# FC_V3_0_SCH_2021-06-05_17-42-28.net
KiCad netlist of a schematic drawn in Altium Designer
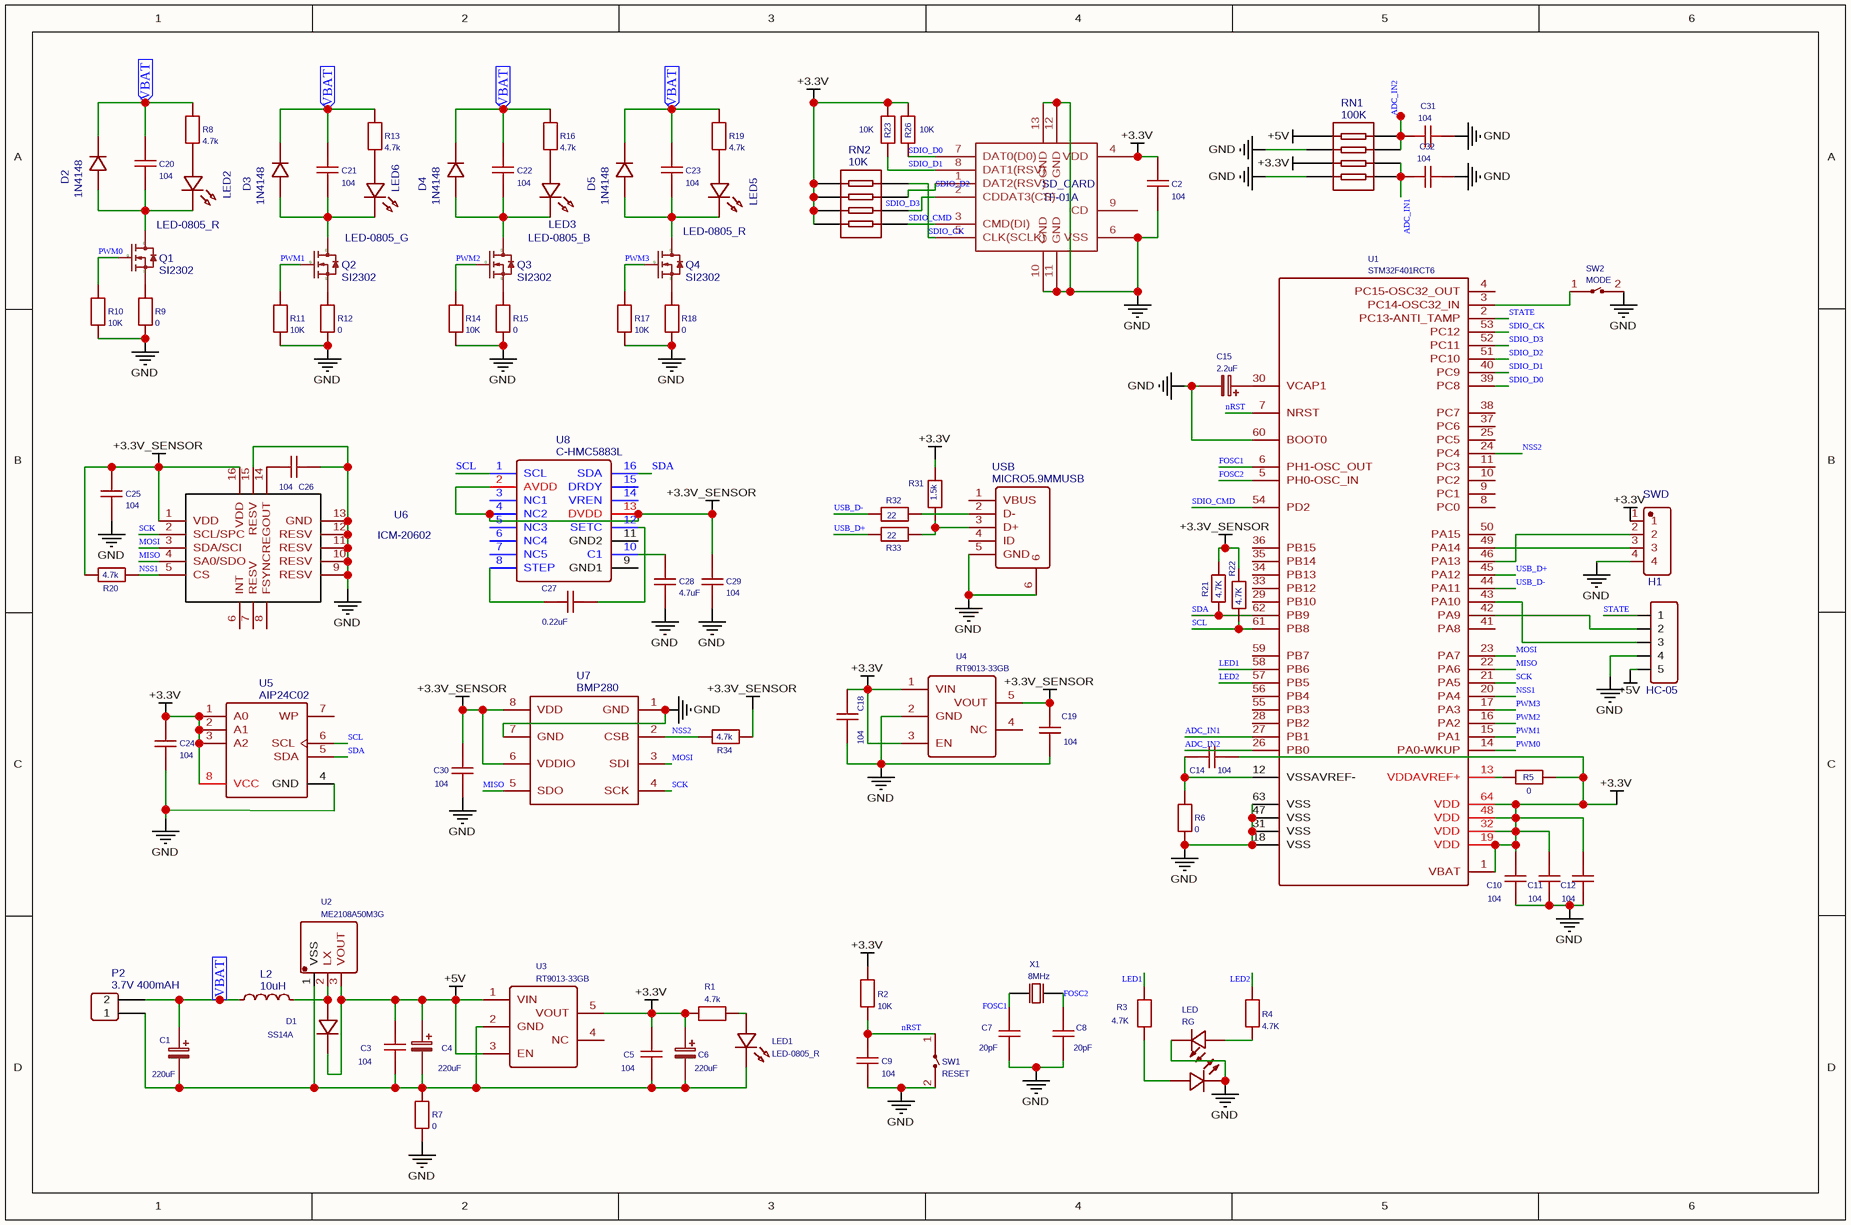
[diagram p0: FC_V3_0_SCH_2021-06-05_17-42-28.schdoc]

(export (version "E")
  (design (tool "Eeschema 10.0.6"))
  (components
    (comp (ref "C1")
      (value "220uF")
      (fields (field (name "CONTRIBUTOR") "LCEDA_Lib"))
      (libsource (lib "altium-import") (part "root_3_220uF_"))
    )
    (comp (ref "C2")
      (value "104")
      (fields (field (name "CONTRIBUTOR") "LCEDA_Lib"))
      (libsource (lib "altium-import") (part "root_1_104_"))
    )
    (comp (ref "C3")
      (value "104")
      (fields (field (name "CONTRIBUTOR") "LCEDA_Lib"))
      (libsource (lib "altium-import") (part "root_1_104_"))
    )
    (comp (ref "C4")
      (value "220uF")
      (fields (field (name "CONTRIBUTOR") "LCEDA_Lib"))
      (libsource (lib "altium-import") (part "root_3_220uF_"))
    )
    (comp (ref "C5")
      (value "104")
      (fields (field (name "CONTRIBUTOR") "LCEDA_Lib"))
      (libsource (lib "altium-import") (part "root_1_104_"))
    )
    (comp (ref "C6")
      (value "220uF")
      (fields (field (name "CONTRIBUTOR") "LCEDA_Lib"))
      (libsource (lib "altium-import") (part "root_3_220uF_"))
    )
    (comp (ref "C7")
      (value "20pF")
      (fields (field (name "CONTRIBUTOR") "LCEDA_Lib"))
      (libsource (lib "altium-import") (part "root_1_20pF_"))
    )
    (comp (ref "C8")
      (value "20pF")
      (fields (field (name "CONTRIBUTOR") "LCEDA_Lib"))
      (libsource (lib "altium-import") (part "root_1_20pF_"))
    )
    (comp (ref "C9")
      (value "104")
      (fields (field (name "CONTRIBUTOR") "LCEDA_Lib"))
      (libsource (lib "altium-import") (part "root_1_104_"))
    )
    (comp (ref "C10")
      (value "104")
      (fields (field (name "CONTRIBUTOR") "LCEDA_Lib"))
      (libsource (lib "altium-import") (part "root_1_104_"))
    )
    (comp (ref "C11")
      (value "104")
      (fields (field (name "CONTRIBUTOR") "LCEDA_Lib"))
      (libsource (lib "altium-import") (part "root_1_104_"))
    )
    (comp (ref "C12")
      (value "104")
      (fields (field (name "CONTRIBUTOR") "LCEDA_Lib"))
      (libsource (lib "altium-import") (part "root_1_104_"))
    )
    (comp (ref "C14")
      (value "104")
      (fields (field (name "CONTRIBUTOR") "LCEDA_Lib"))
      (libsource (lib "altium-import") (part "root_0_104_"))
    )
    (comp (ref "C15")
      (value "2.2uF")
      (fields (field (name "CONTRIBUTOR") "LCEDA_Lib"))
      (libsource (lib "altium-import") (part "root_2_2.2uF_"))
    )
    (comp (ref "C18")
      (value "104")
      (fields (field (name "CONTRIBUTOR") "LCEDA_Lib"))
      (libsource (lib "altium-import") (part "root_1_104_"))
    )
    (comp (ref "C19")
      (value "104")
      (fields (field (name "CONTRIBUTOR") "LCEDA_Lib"))
      (libsource (lib "altium-import") (part "root_1_104_"))
    )
    (comp (ref "C20")
      (value "104")
      (fields (field (name "CONTRIBUTOR") "LCEDA_Lib"))
      (libsource (lib "altium-import") (part "root_1_104_"))
    )
    (comp (ref "C21")
      (value "104")
      (fields (field (name "CONTRIBUTOR") "LCEDA_Lib"))
      (libsource (lib "altium-import") (part "root_1_104_"))
    )
    (comp (ref "C22")
      (value "104")
      (fields (field (name "CONTRIBUTOR") "LCEDA_Lib"))
      (libsource (lib "altium-import") (part "root_1_104_"))
    )
    (comp (ref "C23")
      (value "104")
      (fields (field (name "CONTRIBUTOR") "LCEDA_Lib"))
      (libsource (lib "altium-import") (part "root_1_104_"))
    )
    (comp (ref "C24")
      (value "104")
      (fields (field (name "CONTRIBUTOR") "LCEDA_Lib"))
      (libsource (lib "altium-import") (part "root_1_104_"))
    )
    (comp (ref "C25")
      (value "104")
      (fields (field (name "CONTRIBUTOR") "LCEDA_Lib"))
      (libsource (lib "altium-import") (part "root_3_104_"))
    )
    (comp (ref "C26")
      (value "104")
      (fields (field (name "CONTRIBUTOR") "LCEDA_Lib"))
      (libsource (lib "altium-import") (part "root_0_104_"))
    )
    (comp (ref "C27")
      (value "0.22uF")
      (fields (field (name "CONTRIBUTOR") "LCEDA_Lib"))
      (libsource (lib "altium-import") (part "root_0_0.22uF_"))
    )
    (comp (ref "C28")
      (value "4.7uF")
      (fields (field (name "CONTRIBUTOR") "LCEDA_Lib"))
      (libsource (lib "altium-import") (part "root_1_4.7uF_"))
    )
    (comp (ref "C29")
      (value "104")
      (fields (field (name "CONTRIBUTOR") "LCEDA_Lib"))
      (libsource (lib "altium-import") (part "root_1_104_"))
    )
    (comp (ref "C30")
      (value "104")
      (fields (field (name "CONTRIBUTOR") "LCEDA_Lib"))
      (libsource (lib "altium-import") (part "root_1_104_"))
    )
    (comp (ref "C31")
      (value "104")
      (fields (field (name "CONTRIBUTOR") "LCEDA_Lib"))
      (libsource (lib "altium-import") (part "root_2_104_"))
    )
    (comp (ref "C32")
      (value "104")
      (fields (field (name "CONTRIBUTOR") "LCEDA_Lib"))
      (libsource (lib "altium-import") (part "root_2_104_"))
    )
    (comp (ref "D1")
      (value "SS14A")
      (fields (field (name "BOM_SUPPLIER PART") "C211770") (field (name "CONTRIBUTOR") "LCSC"))
      (libsource (lib "altium-import") (part "root_1_SS14A_"))
    )
    (comp (ref "D2")
      (value "1N4148")
      (fields (field (name "BOM_SUPPLIER PART") "C14516") (field (name "CONTRIBUTOR") "LCEDA_Lib"))
      (libsource (lib "altium-import") (part "root_1_1N4148_"))
    )
    (comp (ref "D3")
      (value "1N4148")
      (fields (field (name "BOM_SUPPLIER PART") "C14516") (field (name "CONTRIBUTOR") "LCEDA_Lib"))
      (libsource (lib "altium-import") (part "root_1_1N4148_"))
    )
    (comp (ref "D4")
      (value "1N4148")
      (fields (field (name "BOM_SUPPLIER PART") "C14516") (field (name "CONTRIBUTOR") "LCEDA_Lib"))
      (libsource (lib "altium-import") (part "root_1_1N4148_"))
    )
    (comp (ref "D5")
      (value "1N4148")
      (fields (field (name "BOM_SUPPLIER PART") "C14516") (field (name "CONTRIBUTOR") "LCEDA_Lib"))
      (libsource (lib "altium-import") (part "root_1_1N4148_"))
    )
    (comp (ref "H1")
      (value "HC-05")
      (fields (field (name "BOM_SUPPLIER PART") "C50950") (field (name "CONTRIBUTOR") "LCEDA_Lib"))
      (libsource (lib "altium-import") (part "root_0_HC-05_"))
    )
    (comp (ref "L2")
      (value "10uH")
      (fields
        (field (name "BOM_SUPPLIER PART") "C207827")
        (field (name "BOM_MANUFACTURER PART") "SLO0420H1R5MTT")
        (field (name "CONTRIBUTOR") "LCSC")
      )
      (libsource (lib "altium-import") (part "root_0_10uH_"))
    )
    (comp (ref "LED")
      (value "RG")
      (fields
        (field (name "BOM_SUPPLIER PART") "C409778")
        (field (name "BOM_MANUFACTURER PART") "MHP3528URUGCT")
        (field (name "CONTRIBUTOR") "LCSC")
      )
      (libsource (lib "altium-import") (part "root_0_RG_"))
    )
    (comp (ref "LED1")
      (value "LED-0805_R")
      (fields
        (field (name "BOM_MANUFACTURER PART") "17-21SURC/S530-A3/TR8")
        (field (name "BOM_SUPPLIER PART") "C72037")
        (field (name "CONTRIBUTOR") "LCEDA_Lib")
      )
      (libsource (lib "altium-import") (part "root_3_LED-0805_R_"))
    )
    (comp (ref "LED2")
      (value "LED-0805_R")
      (fields
        (field (name "BOM_MANUFACTURER PART") "17-21SURC/S530-A3/TR8")
        (field (name "BOM_SUPPLIER PART") "C72037")
        (field (name "CONTRIBUTOR") "LCEDA_Lib")
      )
      (libsource (lib "altium-import") (part "root_3_LED-0805_R_"))
    )
    (comp (ref "LED3")
      (value "LED-0805_B")
      (fields
        (field (name "BOM_MANUFACTURER PART") "D-B080508B1-KS2")
        (field (name "BOM_SUPPLIER PART") "C108412")
        (field (name "CONTRIBUTOR") "LCEDA_Lib")
      )
      (libsource (lib "altium-import") (part "root_3_LED-0805_B_"))
    )
    (comp (ref "LED5")
      (value "LED-0805_R")
      (fields
        (field (name "BOM_MANUFACTURER PART") "17-21SURC/S530-A3/TR8")
        (field (name "BOM_SUPPLIER PART") "C72037")
        (field (name "CONTRIBUTOR") "LCEDA_Lib")
      )
      (libsource (lib "altium-import") (part "root_3_LED-0805_R_"))
    )
    (comp (ref "LED6")
      (value "LED-0805_G")
      (fields
        (field (name "BOM_MANUFACTURER PART") "NCD0805G1")
        (field (name "BOM_SUPPLIER PART") "C84260")
        (field (name "CONTRIBUTOR") "LCEDA_Lib")
      )
      (libsource (lib "altium-import") (part "root_3_LED-0805_G_"))
    )
    (comp (ref "P2")
      (value "3.7V 400mAH")
      (fields
        (field (name "BOM_MANUFACTURER PART") "2.54mm 1*2P")
        (field (name "BOM_SUPPLIER PART") "C36717")
      )
      (libsource (lib "altium-import") (part "root_2_3.7V 400mAH_"))
    )
    (comp (ref "Q1")
      (value "SI2302")
      (fields (field (name "BOM_SUPPLIER PART") "C181087") (field (name "CONTRIBUTOR") "LCSC"))
      (libsource (lib "altium-import") (part "root_0_SI2302_"))
    )
    (comp (ref "Q2")
      (value "SI2302")
      (fields (field (name "BOM_SUPPLIER PART") "C181087") (field (name "CONTRIBUTOR") "LCSC"))
      (libsource (lib "altium-import") (part "root_0_SI2302_"))
    )
    (comp (ref "Q3")
      (value "SI2302")
      (fields (field (name "BOM_SUPPLIER PART") "C181087") (field (name "CONTRIBUTOR") "LCSC"))
      (libsource (lib "altium-import") (part "root_0_SI2302_"))
    )
    (comp (ref "Q4")
      (value "SI2302")
      (fields (field (name "BOM_SUPPLIER PART") "C181087") (field (name "CONTRIBUTOR") "LCSC"))
      (libsource (lib "altium-import") (part "root_0_SI2302_"))
    )
    (comp (ref "R1")
      (value "4.7k")
      (fields (field (name "CONTRIBUTOR") "LCEDA_Lib"))
      (libsource (lib "altium-import") (part "root_0_4.7k_"))
    )
    (comp (ref "R2")
      (value "10K")
      (fields (field (name "CONTRIBUTOR") "LCEDA_Lib"))
      (libsource (lib "altium-import") (part "root_1_10K_"))
    )
    (comp (ref "R3")
      (value "4.7K")
      (fields (field (name "CONTRIBUTOR") "LCEDA_Lib"))
      (libsource (lib "altium-import") (part "root_1_4.7K_"))
    )
    (comp (ref "R4")
      (value "4.7K")
      (fields (field (name "CONTRIBUTOR") "LCEDA_Lib"))
      (libsource (lib "altium-import") (part "root_1_4.7K_"))
    )
    (comp (ref "R5")
      (value "0")
      (fields (field (name "CONTRIBUTOR") "LCEDA_Lib"))
      (libsource (lib "altium-import") (part "root_0_0_"))
    )
    (comp (ref "R6")
      (value "0")
      (fields (field (name "CONTRIBUTOR") "LCEDA_Lib"))
      (libsource (lib "altium-import") (part "root_3_0_"))
    )
    (comp (ref "R7")
      (value "0")
      (fields (field (name "CONTRIBUTOR") "LCEDA_Lib"))
      (libsource (lib "altium-import") (part "root_3_0_"))
    )
    (comp (ref "R8")
      (value "4.7k")
      (fields (field (name "CONTRIBUTOR") "LCEDA_Lib"))
      (libsource (lib "altium-import") (part "root_1_4.7k_"))
    )
    (comp (ref "R9")
      (value "0")
      (fields (field (name "CONTRIBUTOR") "LCEDA_Lib"))
      (libsource (lib "altium-import") (part "root_3_0_"))
    )
    (comp (ref "R10")
      (value "10K")
      (fields (field (name "CONTRIBUTOR") "LCEDA_Lib"))
      (libsource (lib "altium-import") (part "root_1_10K_"))
    )
    (comp (ref "R11")
      (value "10K")
      (fields (field (name "CONTRIBUTOR") "LCEDA_Lib"))
      (libsource (lib "altium-import") (part "root_1_10K_"))
    )
    (comp (ref "R12")
      (value "0")
      (fields (field (name "CONTRIBUTOR") "LCEDA_Lib"))
      (libsource (lib "altium-import") (part "root_3_0_"))
    )
    (comp (ref "R13")
      (value "4.7k")
      (fields (field (name "CONTRIBUTOR") "LCEDA_Lib"))
      (libsource (lib "altium-import") (part "root_1_4.7k_"))
    )
    (comp (ref "R14")
      (value "10K")
      (fields (field (name "CONTRIBUTOR") "LCEDA_Lib"))
      (libsource (lib "altium-import") (part "root_1_10K_"))
    )
    (comp (ref "R15")
      (value "0")
      (fields (field (name "CONTRIBUTOR") "LCEDA_Lib"))
      (libsource (lib "altium-import") (part "root_3_0_"))
    )
    (comp (ref "R16")
      (value "4.7k")
      (fields (field (name "CONTRIBUTOR") "LCEDA_Lib"))
      (libsource (lib "altium-import") (part "root_1_4.7k_"))
    )
    (comp (ref "R17")
      (value "10K")
      (fields (field (name "CONTRIBUTOR") "LCEDA_Lib"))
      (libsource (lib "altium-import") (part "root_1_10K_"))
    )
    (comp (ref "R18")
      (value "0")
      (fields (field (name "CONTRIBUTOR") "LCEDA_Lib"))
      (libsource (lib "altium-import") (part "root_3_0_"))
    )
    (comp (ref "R19")
      (value "4.7k")
      (fields (field (name "CONTRIBUTOR") "LCEDA_Lib"))
      (libsource (lib "altium-import") (part "root_1_4.7k_"))
    )
    (comp (ref "R20")
      (value "4.7k")
      (fields (field (name "CONTRIBUTOR") "LCEDA_Lib"))
      (libsource (lib "altium-import") (part "root_2_4.7k_"))
    )
    (comp (ref "R21")
      (value "4.7K")
      (fields (field (name "CONTRIBUTOR") "LCEDA_Lib"))
      (libsource (lib "altium-import") (part "root_3_4.7K_"))
    )
    (comp (ref "R22")
      (value "4.7K")
      (fields (field (name "CONTRIBUTOR") "LCEDA_Lib"))
      (libsource (lib "altium-import") (part "root_3_4.7K_"))
    )
    (comp (ref "R23")
      (value "10K")
      (fields (field (name "CONTRIBUTOR") "LCEDA_Lib"))
      (libsource (lib "altium-import") (part "root_3_10K_"))
    )
    (comp (ref "R26")
      (value "10K")
      (fields (field (name "CONTRIBUTOR") "LCEDA_Lib"))
      (libsource (lib "altium-import") (part "root_3_10K_"))
    )
    (comp (ref "R31")
      (value "1.5k")
      (fields (field (name "CONTRIBUTOR") "LCEDA_Lib"))
      (libsource (lib "altium-import") (part "root_1_1.5k_"))
    )
    (comp (ref "R32")
      (value "22")
      (fields (field (name "CONTRIBUTOR") "LCEDA_Lib"))
      (libsource (lib "altium-import") (part "root_2_22_"))
    )
    (comp (ref "R33")
      (value "22")
      (fields (field (name "CONTRIBUTOR") "LCEDA_Lib"))
      (libsource (lib "altium-import") (part "root_2_22_"))
    )
    (comp (ref "R34")
      (value "4.7k")
      (fields (field (name "CONTRIBUTOR") "LCEDA_Lib"))
      (libsource (lib "altium-import") (part "root_2_4.7k_"))
    )
    (comp (ref "RN1")
      (value "100K")
      (fields
        (field (name "BOM_MANUFACTURER PART") "RC-ML08W103JT")
        (field (name "BOM_SUPPLIER PART") "C69593")
        (field (name "CONTRIBUTOR") "LCSC")
      )
      (libsource (lib "altium-import") (part "root_1_100K_"))
    )
    (comp (ref "RN2")
      (value "10K")
      (fields
        (field (name "BOM_MANUFACTURER PART") "RC-ML08W103JT")
        (field (name "BOM_SUPPLIER PART") "C69593")
        (field (name "CONTRIBUTOR") "LCSC")
      )
      (libsource (lib "") (part "root_1_10K__1"))
    )
    (comp (ref "SD_CARD")
      (value "TF-01A")
      (fields (field (name "BOM_SUPPLIER PART") "C91145"))
      (libsource (lib "altium-import") (part "root_0_TF-01A_"))
    )
    (comp (ref "SW1")
      (value "RESET")
      (fields
        (field (name "BOM_SUPPLIER PART") "C2690022")
        (field (name "BOM_MANUFACTURER PART") "K2-1107SR-A4SW-01")
        (field (name "CONTRIBUTOR") "LCSC")
      )
      (libsource (lib "altium-import") (part "root_3_RESET_"))
    )
    (comp (ref "SW2")
      (value "MODE")
      (fields
        (field (name "BOM_SUPPLIER PART") "C2690022")
        (field (name "BOM_MANUFACTURER PART") "K2-1107SR-A4SW-01")
        (field (name "CONTRIBUTOR") "LCSC")
      )
      (libsource (lib "altium-import") (part "root_0_MODE_"))
    )
    (comp (ref "SWD")
      (value "SWD")
      (fields
        (field (name "BOM_SUPPLIER PART") "C2718488")
        (field (name "BOM_MANUFACTURER PART") "2.54-1*4P母")
        (field (name "CONTRIBUTOR") "LCSC")
      )
      (libsource (lib "altium-import") (part "root_0_SWD_"))
    )
    (comp (ref "U1")
      (value "STM32F401RCT6")
      (fields (field (name "BOM_SUPPLIER PART") "C74524"))
      (libsource (lib "altium-import") (part "root_2_STM32F401RCT6_"))
    )
    (comp (ref "U2")
      (value "ME2108A50M3G")
      (fields (field (name "BOM_SUPPLIER PART") "C14839"))
      (libsource (lib "altium-import") (part "root_1_ME2108A50M3G_"))
    )
    (comp (ref "U3")
      (value "RT9013-33GB")
      (fields (field (name "BOM_SUPPLIER PART") "C47773"))
      (libsource (lib "altium-import") (part "root_0_RT9013-33GB_"))
    )
    (comp (ref "U4")
      (value "RT9013-33GB")
      (fields (field (name "BOM_SUPPLIER PART") "C47773"))
      (libsource (lib "altium-import") (part "root_0_RT9013-33GB_"))
    )
    (comp (ref "U5")
      (value "AIP24C02")
      (fields (field (name "BOM_SUPPLIER PART") "C85316"))
      (libsource (lib "altium-import") (part "root_0_AIP24C02_"))
    )
    (comp (ref "U6")
      (value "ICM-20602")
      (fields
        (field (name "BOM_MANUFACTURER PART") "ICM20602")
        (field (name "BOM_SUPPLIER PART") "410-ICM-20602")
        (field (name "CONTRIBUTOR") "bee2363")
      )
      (libsource (lib "altium-import") (part "root_0_ICM-20602_"))
    )
    (comp (ref "U7")
      (value "BMP280")
      (fields (field (name "BOM_SUPPLIER PART") "C83291"))
      (libsource (lib "altium-import") (part "root_0_BMP280_"))
    )
    (comp (ref "U8")
      (value "C-HMC5883L")
      (fields
        (field (name "BOM_MANUFACTURER PART") "HMC5883L")
        (field (name "BOM_SUPPLIER PART") "C15640")
        (field (name "CONTRIBUTOR") "PQG2030PQG")
      )
      (libsource (lib "altium-import") (part "root_0_C-HMC5883L_"))
    )
    (comp (ref "USB")
      (value "MICRO5.9MMUSB")
      (fields
        (field (name "BOM_SUPPLIER PART") "C393940")
        (field (name "BOM_MANUFACTURER PART") "MICRO5.9mmusb")
        (field (name "CONTRIBUTOR") "LCSC")
      )
      (libsource (lib "altium-import") (part "root_0_MICRO5.9MMUSB_"))
    )
    (comp (ref "X1")
      (value "8MHz")
      (fields
        (field (name "BOM_SUPPLIER PART") "C313041")
        (field (name "BOM_MANUFACTURER PART") "ABM2-29.4912MHZ-D4Y-T")
        (field (name "CONTRIBUTOR") "LCSC")
      )
      (libsource (lib "altium-import") (part "root_0_8MHz_"))
    )
  )
  (nets
    (net (code "1") (name "+3.3V") (class "Default")
      (node (ref "C10") (pin "2") (pinfunction "2_2") (pintype "passive"))
      (node (ref "C11") (pin "2") (pinfunction "2_2") (pintype "passive"))
      (node (ref "C12") (pin "2") (pinfunction "2_2") (pintype "passive"))
      (node (ref "C14") (pin "2") (pinfunction "2_2") (pintype "passive"))
      (node (ref "C18") (pin "2") (pinfunction "2_2") (pintype "passive"))
      (node (ref "C2") (pin "2") (pinfunction "2_2") (pintype "passive"))
      (node (ref "C24") (pin "2") (pinfunction "2_2") (pintype "passive"))
      (node (ref "C5") (pin "2") (pinfunction "2_2") (pintype "passive"))
      (node (ref "C6") (pin "1") (pinfunction "1_1") (pintype "passive"))
      (node (ref "R1") (pin "1") (pinfunction "1_1") (pintype "passive"))
      (node (ref "R2") (pin "2") (pinfunction "2_2") (pintype "passive"))
      (node (ref "R23") (pin "1") (pinfunction "1_1") (pintype "passive"))
      (node (ref "R26") (pin "1") (pinfunction "1_1") (pintype "passive"))
      (node (ref "R31") (pin "2") (pinfunction "2_2") (pintype "passive"))
      (node (ref "R5") (pin "2") (pinfunction "2_2") (pintype "passive"))
      (node (ref "RN1") (pin "7") (pinfunction "7_7") (pintype "passive"))
      (node (ref "RN2") (pin "5") (pinfunction "5_5") (pintype "passive"))
      (node (ref "RN2") (pin "6") (pinfunction "6_6") (pintype "passive"))
      (node (ref "RN2") (pin "7") (pinfunction "7_7") (pintype "passive"))
      (node (ref "RN2") (pin "8") (pinfunction "8_8") (pintype "passive"))
      (node (ref "SD_CARD") (pin "4") (pinfunction "VDD_4") (pintype "passive"))
      (node (ref "SWD") (pin "1") (pinfunction "1_1") (pintype "passive"))
      (node (ref "U1") (pin "1") (pinfunction "VBAT_1") (pintype "passive"))
      (node (ref "U1") (pin "19") (pinfunction "VDD_19") (pintype "passive"))
      (node (ref "U1") (pin "32") (pinfunction "VDD_32") (pintype "passive"))
      (node (ref "U1") (pin "48") (pinfunction "VDD_48") (pintype "passive"))
      (node (ref "U1") (pin "64") (pinfunction "VDD_64") (pintype "passive"))
      (node (ref "U3") (pin "5") (pinfunction "VOUT_5") (pintype "passive"))
      (node (ref "U4") (pin "1") (pinfunction "VIN_1") (pintype "passive"))
      (node (ref "U4") (pin "3") (pinfunction "EN_3") (pintype "passive"))
      (node (ref "U5") (pin "1") (pinfunction "A0_1") (pintype "passive"))
      (node (ref "U5") (pin "2") (pinfunction "A1_2") (pintype "passive"))
      (node (ref "U5") (pin "3") (pinfunction "A2_3") (pintype "passive"))
      (node (ref "U5") (pin "8") (pinfunction "VCC_8") (pintype "passive"))
    )
    (net (code "2") (name "+3.3V_SENSOR") (class "Default")
      (node (ref "C19") (pin "2") (pinfunction "2_2") (pintype "passive"))
      (node (ref "C25") (pin "1") (pinfunction "1_1") (pintype "passive"))
      (node (ref "C29") (pin "2") (pinfunction "2_2") (pintype "passive"))
      (node (ref "C30") (pin "2") (pinfunction "2_2") (pintype "passive"))
      (node (ref "R20") (pin "2") (pinfunction "2_2") (pintype "passive"))
      (node (ref "R21") (pin "1") (pinfunction "1_1") (pintype "passive"))
      (node (ref "R22") (pin "1") (pinfunction "1_1") (pintype "passive"))
      (node (ref "R34") (pin "1") (pinfunction "1_1") (pintype "passive"))
      (node (ref "U4") (pin "5") (pinfunction "VOUT_5") (pintype "passive"))
      (node (ref "U6") (pin "1") (pinfunction "VDD_1") (pintype "passive"))
      (node (ref "U6") (pin "16") (pinfunction "VDD_16") (pintype "passive"))
      (node (ref "U7") (pin "6") (pinfunction "VDDIO_6") (pintype "passive"))
      (node (ref "U7") (pin "8") (pinfunction "VDD_8") (pintype "passive"))
      (node (ref "U8") (pin "13") (pinfunction "DVDD_13") (pintype "passive"))
      (node (ref "U8") (pin "2") (pinfunction "AVDD_2") (pintype "passive"))
      (node (ref "U8") (pin "4") (pinfunction "NC2_4") (pintype "passive"))
    )
    (net (code "3") (name "+5V") (class "Default")
      (node (ref "C3") (pin "2") (pinfunction "2_2") (pintype "passive"))
      (node (ref "C4") (pin "1") (pinfunction "1_1") (pintype "passive"))
      (node (ref "D1") (pin "1") (pinfunction "C_1") (pintype "passive"))
      (node (ref "H1") (pin "5") (pinfunction "5_5") (pintype "passive"))
      (node (ref "RN1") (pin "5") (pinfunction "5_5") (pintype "passive"))
      (node (ref "U2") (pin "3") (pinfunction "VOUT_3") (pintype "passive"))
      (node (ref "U3") (pin "1") (pinfunction "VIN_1") (pintype "passive"))
      (node (ref "U3") (pin "3") (pinfunction "EN_3") (pintype "passive"))
    )
    (net (code "4") (name "/ADC_IN1") (class "Default")
      (node (ref "C32") (pin "2") (pinfunction "2_2") (pintype "passive"))
      (node (ref "RN1") (pin "1") (pinfunction "1_1") (pintype "passive"))
      (node (ref "RN1") (pin "2") (pinfunction "2_2") (pintype "passive"))
      (node (ref "U1") (pin "27") (pinfunction "PB1_27") (pintype "passive"))
    )
    (net (code "5") (name "/ADC_IN2") (class "Default")
      (node (ref "C31") (pin "2") (pinfunction "2_2") (pintype "passive"))
      (node (ref "RN1") (pin "3") (pinfunction "3_3") (pintype "passive"))
      (node (ref "RN1") (pin "4") (pinfunction "4_4") (pintype "passive"))
      (node (ref "U1") (pin "26") (pinfunction "PB0_26") (pintype "passive"))
    )
    (net (code "6") (name "/FOSC1") (class "Default")
      (node (ref "C7") (pin "2") (pinfunction "2_2") (pintype "passive"))
      (node (ref "U1") (pin "6") (pinfunction "PH1-OSC_OUT_6") (pintype "passive"))
      (node (ref "X1") (pin "1") (pinfunction "OSC1_1") (pintype "passive"))
    )
    (net (code "7") (name "/FOSC2") (class "Default")
      (node (ref "C8") (pin "2") (pinfunction "2_2") (pintype "passive"))
      (node (ref "U1") (pin "5") (pinfunction "PH0-OSC_IN_5") (pintype "passive"))
      (node (ref "X1") (pin "2") (pinfunction "OSC2_2") (pintype "passive"))
    )
    (net (code "8") (name "/LED1") (class "Default")
      (node (ref "R3") (pin "2") (pinfunction "2_2") (pintype "passive"))
      (node (ref "U1") (pin "58") (pinfunction "PB6_58") (pintype "passive"))
    )
    (net (code "9") (name "/LED2") (class "Default")
      (node (ref "R4") (pin "2") (pinfunction "2_2") (pintype "passive"))
      (node (ref "U1") (pin "57") (pinfunction "PB5_57") (pintype "passive"))
    )
    (net (code "10") (name "/MISO") (class "Default")
      (node (ref "U1") (pin "22") (pinfunction "PA6_22") (pintype "passive"))
      (node (ref "U6") (pin "4") (pinfunction "SA0/SDO_4") (pintype "passive"))
      (node (ref "U7") (pin "5") (pinfunction "SDO_5") (pintype "passive"))
    )
    (net (code "11") (name "/MOSI") (class "Default")
      (node (ref "U1") (pin "23") (pinfunction "PA7_23") (pintype "passive"))
      (node (ref "U6") (pin "3") (pinfunction "SDA/SCI_3") (pintype "passive"))
      (node (ref "U7") (pin "3") (pinfunction "SDI_3") (pintype "passive"))
    )
    (net (code "12") (name "/NSS1") (class "Default")
      (node (ref "R20") (pin "1") (pinfunction "1_1") (pintype "passive"))
      (node (ref "U1") (pin "20") (pinfunction "PA4_20") (pintype "passive"))
      (node (ref "U6") (pin "5") (pinfunction "CS_5") (pintype "passive"))
    )
    (net (code "13") (name "/NSS2") (class "Default")
      (node (ref "R34") (pin "2") (pinfunction "2_2") (pintype "passive"))
      (node (ref "U1") (pin "24") (pinfunction "PC4_24") (pintype "passive"))
      (node (ref "U7") (pin "2") (pinfunction "CSB_2") (pintype "passive"))
    )
    (net (code "14") (name "/PWM0") (class "Default")
      (node (ref "Q1") (pin "1") (pinfunction "G_1") (pintype "passive"))
      (node (ref "R10") (pin "2") (pinfunction "2_2") (pintype "passive"))
      (node (ref "U1") (pin "14") (pinfunction "PA0-WKUP_14") (pintype "passive"))
    )
    (net (code "15") (name "/PWM1") (class "Default")
      (node (ref "Q2") (pin "1") (pinfunction "G_1") (pintype "passive"))
      (node (ref "R11") (pin "2") (pinfunction "2_2") (pintype "passive"))
      (node (ref "U1") (pin "15") (pinfunction "PA1_15") (pintype "passive"))
    )
    (net (code "16") (name "/PWM2") (class "Default")
      (node (ref "Q3") (pin "1") (pinfunction "G_1") (pintype "passive"))
      (node (ref "R14") (pin "2") (pinfunction "2_2") (pintype "passive"))
      (node (ref "U1") (pin "16") (pinfunction "PA2_16") (pintype "passive"))
    )
    (net (code "17") (name "/PWM3") (class "Default")
      (node (ref "Q4") (pin "1") (pinfunction "G_1") (pintype "passive"))
      (node (ref "R17") (pin "2") (pinfunction "2_2") (pintype "passive"))
      (node (ref "U1") (pin "17") (pinfunction "PA3_17") (pintype "passive"))
    )
    (net (code "18") (name "/SCK") (class "Default")
      (node (ref "U1") (pin "21") (pinfunction "PA5_21") (pintype "passive"))
      (node (ref "U6") (pin "2") (pinfunction "SCL/SPC_2") (pintype "passive"))
      (node (ref "U7") (pin "4") (pinfunction "SCK_4") (pintype "passive"))
    )
    (net (code "19") (name "/SCL") (class "Default")
      (node (ref "R22") (pin "2") (pinfunction "2_2") (pintype "passive"))
      (node (ref "U1") (pin "61") (pinfunction "PB8_61") (pintype "passive"))
      (node (ref "U5") (pin "6") (pinfunction "SCL_6") (pintype "passive"))
      (node (ref "U8") (pin "1") (pinfunction "SCL_1") (pintype "passive"))
    )
    (net (code "20") (name "/SDA") (class "Default")
      (node (ref "R21") (pin "2") (pinfunction "2_2") (pintype "passive"))
      (node (ref "U1") (pin "62") (pinfunction "PB9_62") (pintype "passive"))
      (node (ref "U5") (pin "5") (pinfunction "SDA_5") (pintype "passive"))
      (node (ref "U8") (pin "16") (pinfunction "SDA_16") (pintype "passive"))
    )
    (net (code "21") (name "/SDIO_CK") (class "Default")
      (node (ref "RN2") (pin "4") (pinfunction "4_4") (pintype "passive"))
      (node (ref "SD_CARD") (pin "5") (pinfunction "CLK(SCLK)_5") (pintype "passive"))
      (node (ref "U1") (pin "53") (pinfunction "PC12_53") (pintype "passive"))
    )
    (net (code "22") (name "/SDIO_CMD") (class "Default")
      (node (ref "RN2") (pin "1") (pinfunction "1_1") (pintype "passive"))
      (node (ref "SD_CARD") (pin "3") (pinfunction "CMD(DI)_3") (pintype "passive"))
      (node (ref "U1") (pin "54") (pinfunction "PD2_54") (pintype "passive"))
    )
    (net (code "23") (name "/SDIO_D0") (class "Default")
      (node (ref "R26") (pin "2") (pinfunction "2_2") (pintype "passive"))
      (node (ref "SD_CARD") (pin "7") (pinfunction "DAT0(D0)_7") (pintype "passive"))
      (node (ref "U1") (pin "39") (pinfunction "PC8_39") (pintype "passive"))
    )
    (net (code "24") (name "/SDIO_D1") (class "Default")
      (node (ref "R23") (pin "2") (pinfunction "2_2") (pintype "passive"))
      (node (ref "SD_CARD") (pin "8") (pinfunction "DAT1(RSV)_8") (pintype "passive"))
      (node (ref "U1") (pin "40") (pinfunction "PC9_40") (pintype "passive"))
    )
    (net (code "25") (name "/SDIO_D2") (class "Default")
      (node (ref "RN2") (pin "3") (pinfunction "3_3") (pintype "passive"))
      (node (ref "SD_CARD") (pin "1") (pinfunction "DAT2(RSV)_1") (pintype "passive"))
      (node (ref "U1") (pin "51") (pinfunction "PC10_51") (pintype "passive"))
    )
    (net (code "26") (name "/SDIO_D3") (class "Default")
      (node (ref "RN2") (pin "2") (pinfunction "2_2") (pintype "passive"))
      (node (ref "SD_CARD") (pin "2") (pinfunction "CDDAT3(CS)_2") (pintype "passive"))
      (node (ref "U1") (pin "52") (pinfunction "PC11_52") (pintype "passive"))
    )
    (net (code "27") (name "/STATE") (class "Default")
      (node (ref "H1") (pin "1") (pinfunction "1_1") (pintype "passive"))
      (node (ref "U1") (pin "2") (pinfunction "PC13-ANTI_TAMP_2") (pintype "passive"))
    )
    (net (code "28") (name "/USB_D+") (class "Default")
      (node (ref "R33") (pin "2") (pinfunction "2_2") (pintype "passive"))
      (node (ref "U1") (pin "45") (pinfunction "PA12_45") (pintype "passive"))
    )
    (net (code "29") (name "/USB_D-") (class "Default")
      (node (ref "R32") (pin "2") (pinfunction "2_2") (pintype "passive"))
      (node (ref "U1") (pin "44") (pinfunction "PA11_44") (pintype "passive"))
    )
    (net (code "30") (name "/VBAT") (class "Default")
      (node (ref "C1") (pin "1") (pinfunction "1_1") (pintype "passive"))
      (node (ref "C20") (pin "2") (pinfunction "2_2") (pintype "passive"))
      (node (ref "C21") (pin "2") (pinfunction "2_2") (pintype "passive"))
      (node (ref "C22") (pin "2") (pinfunction "2_2") (pintype "passive"))
      (node (ref "C23") (pin "2") (pinfunction "2_2") (pintype "passive"))
      (node (ref "D2") (pin "2") (pinfunction "2_2") (pintype "passive"))
      (node (ref "D3") (pin "2") (pinfunction "2_2") (pintype "passive"))
      (node (ref "D4") (pin "2") (pinfunction "2_2") (pintype "passive"))
      (node (ref "D5") (pin "2") (pinfunction "2_2") (pintype "passive"))
      (node (ref "L2") (pin "1") (pinfunction "1_1") (pintype "passive"))
      (node (ref "P2") (pin "2") (pinfunction "2_2") (pintype "passive"))
      (node (ref "R13") (pin "2") (pinfunction "2_2") (pintype "passive"))
      (node (ref "R16") (pin "2") (pinfunction "2_2") (pintype "passive"))
      (node (ref "R19") (pin "2") (pinfunction "2_2") (pintype "passive"))
      (node (ref "R8") (pin "2") (pinfunction "2_2") (pintype "passive"))
    )
    (net (code "31") (name "/nRST") (class "Default")
      (node (ref "C9") (pin "2") (pinfunction "2_2") (pintype "passive"))
      (node (ref "R2") (pin "1") (pinfunction "1_1") (pintype "passive"))
      (node (ref "SW1") (pin "1") (pinfunction "1_1") (pintype "passive"))
      (node (ref "U1") (pin "7") (pinfunction "NRST_7") (pintype "passive"))
    )
    (net (code "32") (name "GND") (class "Default")
      (node (ref "C10") (pin "1") (pinfunction "1_1") (pintype "passive"))
      (node (ref "C11") (pin "1") (pinfunction "1_1") (pintype "passive"))
      (node (ref "C12") (pin "1") (pinfunction "1_1") (pintype "passive"))
      (node (ref "C15") (pin "2") (pinfunction "2_2") (pintype "passive"))
      (node (ref "C18") (pin "1") (pinfunction "1_1") (pintype "passive"))
      (node (ref "C19") (pin "1") (pinfunction "1_1") (pintype "passive"))
      (node (ref "C2") (pin "1") (pinfunction "1_1") (pintype "passive"))
      (node (ref "C24") (pin "1") (pinfunction "1_1") (pintype "passive"))
      (node (ref "C25") (pin "2") (pinfunction "2_2") (pintype "passive"))
      (node (ref "C26") (pin "2") (pinfunction "2_2") (pintype "passive"))
      (node (ref "C28") (pin "1") (pinfunction "1_1") (pintype "passive"))
      (node (ref "C29") (pin "1") (pinfunction "1_1") (pintype "passive"))
      (node (ref "C30") (pin "1") (pinfunction "1_1") (pintype "passive"))
      (node (ref "C31") (pin "1") (pinfunction "1_1") (pintype "passive"))
      (node (ref "C32") (pin "1") (pinfunction "1_1") (pintype "passive"))
      (node (ref "C7") (pin "1") (pinfunction "1_1") (pintype "passive"))
      (node (ref "C8") (pin "1") (pinfunction "1_1") (pintype "passive"))
      (node (ref "C9") (pin "1") (pinfunction "1_1") (pintype "passive"))
      (node (ref "H1") (pin "4") (pinfunction "4_4") (pintype "passive"))
      (node (ref "LED") (pin "2") (pinfunction "-_2") (pintype "passive"))
      (node (ref "LED") (pin "4") (pinfunction "-_4") (pintype "passive"))
      (node (ref "R10") (pin "1") (pinfunction "1_1") (pintype "passive"))
      (node (ref "R11") (pin "1") (pinfunction "1_1") (pintype "passive"))
      (node (ref "R12") (pin "2") (pinfunction "2_2") (pintype "passive"))
      (node (ref "R14") (pin "1") (pinfunction "1_1") (pintype "passive"))
      (node (ref "R15") (pin "2") (pinfunction "2_2") (pintype "passive"))
      (node (ref "R17") (pin "1") (pinfunction "1_1") (pintype "passive"))
      (node (ref "R18") (pin "2") (pinfunction "2_2") (pintype "passive"))
      (node (ref "R6") (pin "2") (pinfunction "2_2") (pintype "passive"))
      (node (ref "R7") (pin "2") (pinfunction "2_2") (pintype "passive"))
      (node (ref "R9") (pin "2") (pinfunction "2_2") (pintype "passive"))
      (node (ref "RN1") (pin "6") (pinfunction "6_6") (pintype "passive"))
      (node (ref "RN1") (pin "8") (pinfunction "8_8") (pintype "passive"))
      (node (ref "SD_CARD") (pin "10") (pinfunction "GND_10") (pintype "passive"))
      (node (ref "SD_CARD") (pin "11") (pinfunction "GND_11") (pintype "passive"))
      (node (ref "SD_CARD") (pin "12") (pinfunction "GND_12") (pintype "passive"))
      (node (ref "SD_CARD") (pin "13") (pinfunction "GND_13") (pintype "passive"))
      (node (ref "SD_CARD") (pin "6") (pinfunction "VSS_6") (pintype "passive"))
      (node (ref "SW1") (pin "2") (pinfunction "2_2") (pintype "passive"))
      (node (ref "SW2") (pin "2") (pinfunction "2_2") (pintype "passive"))
      (node (ref "SWD") (pin "4") (pinfunction "4_4") (pintype "passive"))
      (node (ref "U1") (pin "18") (pinfunction "VSS_18") (pintype "passive"))
      (node (ref "U1") (pin "31") (pinfunction "VSS_31") (pintype "passive"))
      (node (ref "U1") (pin "47") (pinfunction "VSS_47") (pintype "passive"))
      (node (ref "U1") (pin "60") (pinfunction "BOOT0_60") (pintype "passive"))
      (node (ref "U1") (pin "63") (pinfunction "VSS_63") (pintype "passive"))
      (node (ref "U4") (pin "2") (pinfunction "GND_2") (pintype "passive"))
      (node (ref "U5") (pin "4") (pinfunction "GND_4") (pintype "passive"))
      (node (ref "U6") (pin "10") (pinfunction "RESV_10") (pintype "passive"))
      (node (ref "U6") (pin "11") (pinfunction "RESV_11") (pintype "passive"))
      (node (ref "U6") (pin "12") (pinfunction "RESV_12") (pintype "passive"))
      (node (ref "U6") (pin "13") (pinfunction "GND_13") (pintype "passive"))
      (node (ref "U6") (pin "15") (pinfunction "RESV_15") (pintype "passive"))
      (node (ref "U6") (pin "9") (pinfunction "RESV_9") (pintype "passive"))
      (node (ref "U7") (pin "1") (pinfunction "GND_1") (pintype "passive"))
      (node (ref "U7") (pin "7") (pinfunction "GND_7") (pintype "passive"))
      (node (ref "USB") (pin "5") (pinfunction "GND_5") (pintype "passive"))
      (node (ref "USB") (pin "6") (pinfunction "6_6") (pintype "passive"))
    )
    (net (code "33") (name "Net-(D1-A)") (class "Default")
      (node (ref "D1") (pin "2") (pinfunction "A_2") (pintype "passive"))
      (node (ref "L2") (pin "2") (pinfunction "2_2") (pintype "passive"))
      (node (ref "U2") (pin "2") (pinfunction "LX_2") (pintype "passive"))
    )
    (net (code "34") (name "Net-(LED-+-Pad1)") (class "Default")
      (node (ref "LED") (pin "1") (pinfunction "+_1") (pintype "passive"))
      (node (ref "R3") (pin "1") (pinfunction "1_1") (pintype "passive"))
    )
    (net (code "35") (name "Net-(LED-+-Pad3)") (class "Default")
      (node (ref "LED") (pin "3") (pinfunction "+_3") (pintype "passive"))
      (node (ref "R4") (pin "1") (pinfunction "1_1") (pintype "passive"))
    )
    (net (code "36") (name "Net-(LED1-Pad1)") (class "Default")
      (node (ref "LED1") (pin "1") (pinfunction "1_1") (pintype "passive"))
      (node (ref "R1") (pin "2") (pinfunction "2_2") (pintype "passive"))
    )
    (net (code "37") (name "Net-(LED2-Pad1)") (class "Default")
      (node (ref "LED2") (pin "1") (pinfunction "1_1") (pintype "passive"))
      (node (ref "R8") (pin "1") (pinfunction "1_1") (pintype "passive"))
    )
    (net (code "38") (name "Net-(LED3-Pad1)") (class "Default")
      (node (ref "LED3") (pin "1") (pinfunction "1_1") (pintype "passive"))
      (node (ref "R16") (pin "1") (pinfunction "1_1") (pintype "passive"))
    )
    (net (code "39") (name "Net-(LED5-Pad1)") (class "Default")
      (node (ref "LED5") (pin "1") (pinfunction "1_1") (pintype "passive"))
      (node (ref "R19") (pin "1") (pinfunction "1_1") (pintype "passive"))
    )
    (net (code "40") (name "Net-(LED6-Pad1)") (class "Default")
      (node (ref "LED6") (pin "1") (pinfunction "1_1") (pintype "passive"))
      (node (ref "R13") (pin "1") (pinfunction "1_1") (pintype "passive"))
    )
    (net (code "41") (name "Net-(Q1-D)") (class "Default")
      (node (ref "C20") (pin "1") (pinfunction "1_1") (pintype "passive"))
      (node (ref "D2") (pin "1") (pinfunction "1_1") (pintype "passive"))
      (node (ref "LED2") (pin "2") (pinfunction "2_2") (pintype "passive"))
      (node (ref "Q1") (pin "3") (pinfunction "D_3") (pintype "passive"))
    )
    (net (code "42") (name "Net-(Q1-S)") (class "Default")
      (node (ref "Q1") (pin "2") (pinfunction "S_2") (pintype "passive"))
      (node (ref "R9") (pin "1") (pinfunction "1_1") (pintype "passive"))
    )
    (net (code "43") (name "Net-(Q2-D)") (class "Default")
      (node (ref "C21") (pin "1") (pinfunction "1_1") (pintype "passive"))
      (node (ref "D3") (pin "1") (pinfunction "1_1") (pintype "passive"))
      (node (ref "LED6") (pin "2") (pinfunction "2_2") (pintype "passive"))
      (node (ref "Q2") (pin "3") (pinfunction "D_3") (pintype "passive"))
    )
    (net (code "44") (name "Net-(Q2-S)") (class "Default")
      (node (ref "Q2") (pin "2") (pinfunction "S_2") (pintype "passive"))
      (node (ref "R12") (pin "1") (pinfunction "1_1") (pintype "passive"))
    )
    (net (code "45") (name "Net-(Q3-D)") (class "Default")
      (node (ref "C22") (pin "1") (pinfunction "1_1") (pintype "passive"))
      (node (ref "D4") (pin "1") (pinfunction "1_1") (pintype "passive"))
      (node (ref "LED3") (pin "2") (pinfunction "2_2") (pintype "passive"))
      (node (ref "Q3") (pin "3") (pinfunction "D_3") (pintype "passive"))
    )
    (net (code "46") (name "Net-(Q3-S)") (class "Default")
      (node (ref "Q3") (pin "2") (pinfunction "S_2") (pintype "passive"))
      (node (ref "R15") (pin "1") (pinfunction "1_1") (pintype "passive"))
    )
    (net (code "47") (name "Net-(Q4-D)") (class "Default")
      (node (ref "C23") (pin "1") (pinfunction "1_1") (pintype "passive"))
      (node (ref "D5") (pin "1") (pinfunction "1_1") (pintype "passive"))
      (node (ref "LED5") (pin "2") (pinfunction "2_2") (pintype "passive"))
      (node (ref "Q4") (pin "3") (pinfunction "D_3") (pintype "passive"))
    )
    (net (code "48") (name "Net-(Q4-S)") (class "Default")
      (node (ref "Q4") (pin "2") (pinfunction "S_2") (pintype "passive"))
      (node (ref "R18") (pin "1") (pinfunction "1_1") (pintype "passive"))
    )
    (net (code "49") (name "Net-(U1-PA9)") (class "Default")
      (node (ref "H1") (pin "2") (pinfunction "2_2") (pintype "passive"))
      (node (ref "U1") (pin "42") (pinfunction "PA9_42") (pintype "passive"))
    )
    (net (code "50") (name "Net-(U1-PA10)") (class "Default")
      (node (ref "H1") (pin "3") (pinfunction "3_3") (pintype "passive"))
      (node (ref "U1") (pin "43") (pinfunction "PA10_43") (pintype "passive"))
    )
    (net (code "51") (name "Net-(U1-PA13)") (class "Default")
      (node (ref "SWD") (pin "2") (pinfunction "2_2") (pintype "passive"))
      (node (ref "U1") (pin "46") (pinfunction "PA13_46") (pintype "passive"))
    )
    (net (code "52") (name "Net-(U1-PA14)") (class "Default")
      (node (ref "SWD") (pin "3") (pinfunction "3_3") (pintype "passive"))
      (node (ref "U1") (pin "49") (pinfunction "PA14_49") (pintype "passive"))
    )
    (net (code "53") (name "Net-(U1-PC14-OSC32_IN)") (class "Default")
      (node (ref "SW2") (pin "1") (pinfunction "1_1") (pintype "passive"))
      (node (ref "U1") (pin "3") (pinfunction "PC14-OSC32_IN_3") (pintype "passive"))
    )
    (net (code "54") (name "Net-(U1-VCAP1)") (class "Default")
      (node (ref "C15") (pin "1") (pinfunction "1_1") (pintype "passive"))
      (node (ref "U1") (pin "30") (pinfunction "VCAP1_30") (pintype "passive"))
    )
    (net (code "55") (name "Net-(U1-VDDAVREF+)") (class "Default")
      (node (ref "R5") (pin "1") (pinfunction "1_1") (pintype "passive"))
      (node (ref "U1") (pin "13") (pinfunction "VDDAVREF+_13") (pintype "passive"))
    )
    (net (code "56") (name "Net-(U1-VSSAVREF-)") (class "Default")
      (node (ref "C14") (pin "1") (pinfunction "1_1") (pintype "passive"))
      (node (ref "R6") (pin "1") (pinfunction "1_1") (pintype "passive"))
      (node (ref "U1") (pin "12") (pinfunction "VSSAVREF-_12") (pintype "passive"))
    )
    (net (code "57") (name "Net-(U2-VSS)") (class "Default")
      (node (ref "C1") (pin "2") (pinfunction "2_2") (pintype "passive"))
      (node (ref "C3") (pin "1") (pinfunction "1_1") (pintype "passive"))
      (node (ref "C4") (pin "2") (pinfunction "2_2") (pintype "passive"))
      (node (ref "C5") (pin "1") (pinfunction "1_1") (pintype "passive"))
      (node (ref "C6") (pin "2") (pinfunction "2_2") (pintype "passive"))
      (node (ref "LED1") (pin "2") (pinfunction "2_2") (pintype "passive"))
      (node (ref "P2") (pin "1") (pinfunction "1_1") (pintype "passive"))
      (node (ref "R7") (pin "1") (pinfunction "1_1") (pintype "passive"))
      (node (ref "U2") (pin "1") (pinfunction "VSS_1") (pintype "passive"))
      (node (ref "U3") (pin "2") (pinfunction "GND_2") (pintype "passive"))
    )
    (net (code "58") (name "Net-(U6-REGOUT)") (class "Default")
      (node (ref "C26") (pin "1") (pinfunction "1_1") (pintype "passive"))
      (node (ref "U6") (pin "14") (pinfunction "REGOUT_14") (pintype "passive"))
    )
    (net (code "59") (name "Net-(U8-C1)") (class "Default")
      (node (ref "C28") (pin "2") (pinfunction "2_2") (pintype "passive"))
      (node (ref "U8") (pin "10") (pinfunction "C1_10") (pintype "passive"))
    )
    (net (code "60") (name "Net-(U8-SETC)") (class "Default")
      (node (ref "C27") (pin "2") (pinfunction "2_2") (pintype "passive"))
      (node (ref "U8") (pin "12") (pinfunction "SETC_12") (pintype "passive"))
    )
    (net (code "61") (name "Net-(U8-STEP)") (class "Default")
      (node (ref "C27") (pin "1") (pinfunction "1_1") (pintype "passive"))
      (node (ref "U8") (pin "8") (pinfunction "STEP_8") (pintype "passive"))
    )
    (net (code "62") (name "Net-(USB-D+)") (class "Default")
      (node (ref "R31") (pin "1") (pinfunction "1_1") (pintype "passive"))
      (node (ref "R33") (pin "1") (pinfunction "1_1") (pintype "passive"))
      (node (ref "USB") (pin "3") (pinfunction "D+_3") (pintype "passive"))
    )
    (net (code "63") (name "Net-(USB-D-)") (class "Default")
      (node (ref "R32") (pin "1") (pinfunction "1_1") (pintype "passive"))
      (node (ref "USB") (pin "2") (pinfunction "D-_2") (pintype "passive"))
    )
    (net (code "64") (name "unconnected-(SD_CARD-CD-Pad9)") (class "Default")
      (node (ref "SD_CARD") (pin "9") (pinfunction "CD_9") (pintype "passive"))
    )
    (net (code "65") (name "unconnected-(U1-PA8-Pad41)") (class "Default")
      (node (ref "U1") (pin "41") (pinfunction "PA8_41") (pintype "passive"))
    )
    (net (code "66") (name "unconnected-(U1-PA15-Pad50)") (class "Default")
      (node (ref "U1") (pin "50") (pinfunction "PA15_50") (pintype "passive"))
    )
    (net (code "67") (name "unconnected-(U1-PB2-Pad28)") (class "Default")
      (node (ref "U1") (pin "28") (pinfunction "PB2_28") (pintype "passive"))
    )
    (net (code "68") (name "unconnected-(U1-PB3-Pad55)") (class "Default")
      (node (ref "U1") (pin "55") (pinfunction "PB3_55") (pintype "passive"))
    )
    (net (code "69") (name "unconnected-(U1-PB4-Pad56)") (class "Default")
      (node (ref "U1") (pin "56") (pinfunction "PB4_56") (pintype "passive"))
    )
    (net (code "70") (name "unconnected-(U1-PB7-Pad59)") (class "Default")
      (node (ref "U1") (pin "59") (pinfunction "PB7_59") (pintype "passive"))
    )
    (net (code "71") (name "unconnected-(U1-PB10-Pad29)") (class "Default")
      (node (ref "U1") (pin "29") (pinfunction "PB10_29") (pintype "passive"))
    )
    (net (code "72") (name "unconnected-(U1-PB12-Pad33)") (class "Default")
      (node (ref "U1") (pin "33") (pinfunction "PB12_33") (pintype "passive"))
    )
    (net (code "73") (name "unconnected-(U1-PB13-Pad34)") (class "Default")
      (node (ref "U1") (pin "34") (pinfunction "PB13_34") (pintype "passive"))
    )
    (net (code "74") (name "unconnected-(U1-PB14-Pad35)") (class "Default")
      (node (ref "U1") (pin "35") (pinfunction "PB14_35") (pintype "passive"))
    )
    (net (code "75") (name "unconnected-(U1-PB15-Pad36)") (class "Default")
      (node (ref "U1") (pin "36") (pinfunction "PB15_36") (pintype "passive"))
    )
    (net (code "76") (name "unconnected-(U1-PC0-Pad8)") (class "Default")
      (node (ref "U1") (pin "8") (pinfunction "PC0_8") (pintype "passive"))
    )
    (net (code "77") (name "unconnected-(U1-PC1-Pad9)") (class "Default")
      (node (ref "U1") (pin "9") (pinfunction "PC1_9") (pintype "passive"))
    )
    (net (code "78") (name "unconnected-(U1-PC2-Pad10)") (class "Default")
      (node (ref "U1") (pin "10") (pinfunction "PC2_10") (pintype "passive"))
    )
    (net (code "79") (name "unconnected-(U1-PC3-Pad11)") (class "Default")
      (node (ref "U1") (pin "11") (pinfunction "PC3_11") (pintype "passive"))
    )
    (net (code "80") (name "unconnected-(U1-PC5-Pad25)") (class "Default")
      (node (ref "U1") (pin "25") (pinfunction "PC5_25") (pintype "passive"))
    )
    (net (code "81") (name "unconnected-(U1-PC6-Pad37)") (class "Default")
      (node (ref "U1") (pin "37") (pinfunction "PC6_37") (pintype "passive"))
    )
    (net (code "82") (name "unconnected-(U1-PC7-Pad38)") (class "Default")
      (node (ref "U1") (pin "38") (pinfunction "PC7_38") (pintype "passive"))
    )
    (net (code "83") (name "unconnected-(U1-PC15-OSC32_OUT-Pad4)") (class "Default")
      (node (ref "U1") (pin "4") (pinfunction "PC15-OSC32_OUT_4") (pintype "passive"))
    )
    (net (code "84") (name "unconnected-(U3-NC-Pad4)") (class "Default")
      (node (ref "U3") (pin "4") (pinfunction "NC_4") (pintype "passive"))
    )
    (net (code "85") (name "unconnected-(U4-NC-Pad4)") (class "Default")
      (node (ref "U4") (pin "4") (pinfunction "NC_4") (pintype "passive"))
    )
    (net (code "86") (name "unconnected-(U5-WP-Pad7)") (class "Default")
      (node (ref "U5") (pin "7") (pinfunction "WP_7") (pintype "passive"))
    )
    (net (code "87") (name "unconnected-(U6-FSYNC-Pad8)") (class "Default")
      (node (ref "U6") (pin "8") (pinfunction "FSYNC_8") (pintype "passive"))
    )
    (net (code "88") (name "unconnected-(U6-INT-Pad6)") (class "Default")
      (node (ref "U6") (pin "6") (pinfunction "INT_6") (pintype "passive"))
    )
    (net (code "89") (name "unconnected-(U6-RESV-Pad7)") (class "Default")
      (node (ref "U6") (pin "7") (pinfunction "RESV_7") (pintype "passive"))
    )
    (net (code "90") (name "unconnected-(U8-DRDY-Pad15)") (class "Default")
      (node (ref "U8") (pin "15") (pinfunction "DRDY_15") (pintype "passive"))
    )
    (net (code "91") (name "unconnected-(U8-GND1-Pad9)") (class "Default")
      (node (ref "U8") (pin "9") (pinfunction "GND1_9") (pintype "passive"))
    )
    (net (code "92") (name "unconnected-(U8-GND2-Pad11)") (class "Default")
      (node (ref "U8") (pin "11") (pinfunction "GND2_11") (pintype "passive"))
    )
    (net (code "93") (name "unconnected-(U8-NC1-Pad3)") (class "Default")
      (node (ref "U8") (pin "3") (pinfunction "NC1_3") (pintype "passive"))
    )
    (net (code "94") (name "unconnected-(U8-NC3-Pad5)") (class "Default")
      (node (ref "U8") (pin "5") (pinfunction "NC3_5") (pintype "passive"))
    )
    (net (code "95") (name "unconnected-(U8-NC4-Pad6)") (class "Default")
      (node (ref "U8") (pin "6") (pinfunction "NC4_6") (pintype "passive"))
    )
    (net (code "96") (name "unconnected-(U8-NC5-Pad7)") (class "Default")
      (node (ref "U8") (pin "7") (pinfunction "NC5_7") (pintype "passive"))
    )
    (net (code "97") (name "unconnected-(U8-VREN-Pad14)") (class "Default")
      (node (ref "U8") (pin "14") (pinfunction "VREN_14") (pintype "passive"))
    )
    (net (code "98") (name "unconnected-(USB-ID-Pad4)") (class "Default")
      (node (ref "USB") (pin "4") (pinfunction "ID_4") (pintype "passive"))
    )
    (net (code "99") (name "unconnected-(USB-VBUS-Pad1)") (class "Default")
      (node (ref "USB") (pin "1") (pinfunction "VBUS_1") (pintype "passive"))
    )
  )
)
